# SCH_ad7606__2022-06-28.net
KiCad netlist of a schematic drawn in EasyEDA
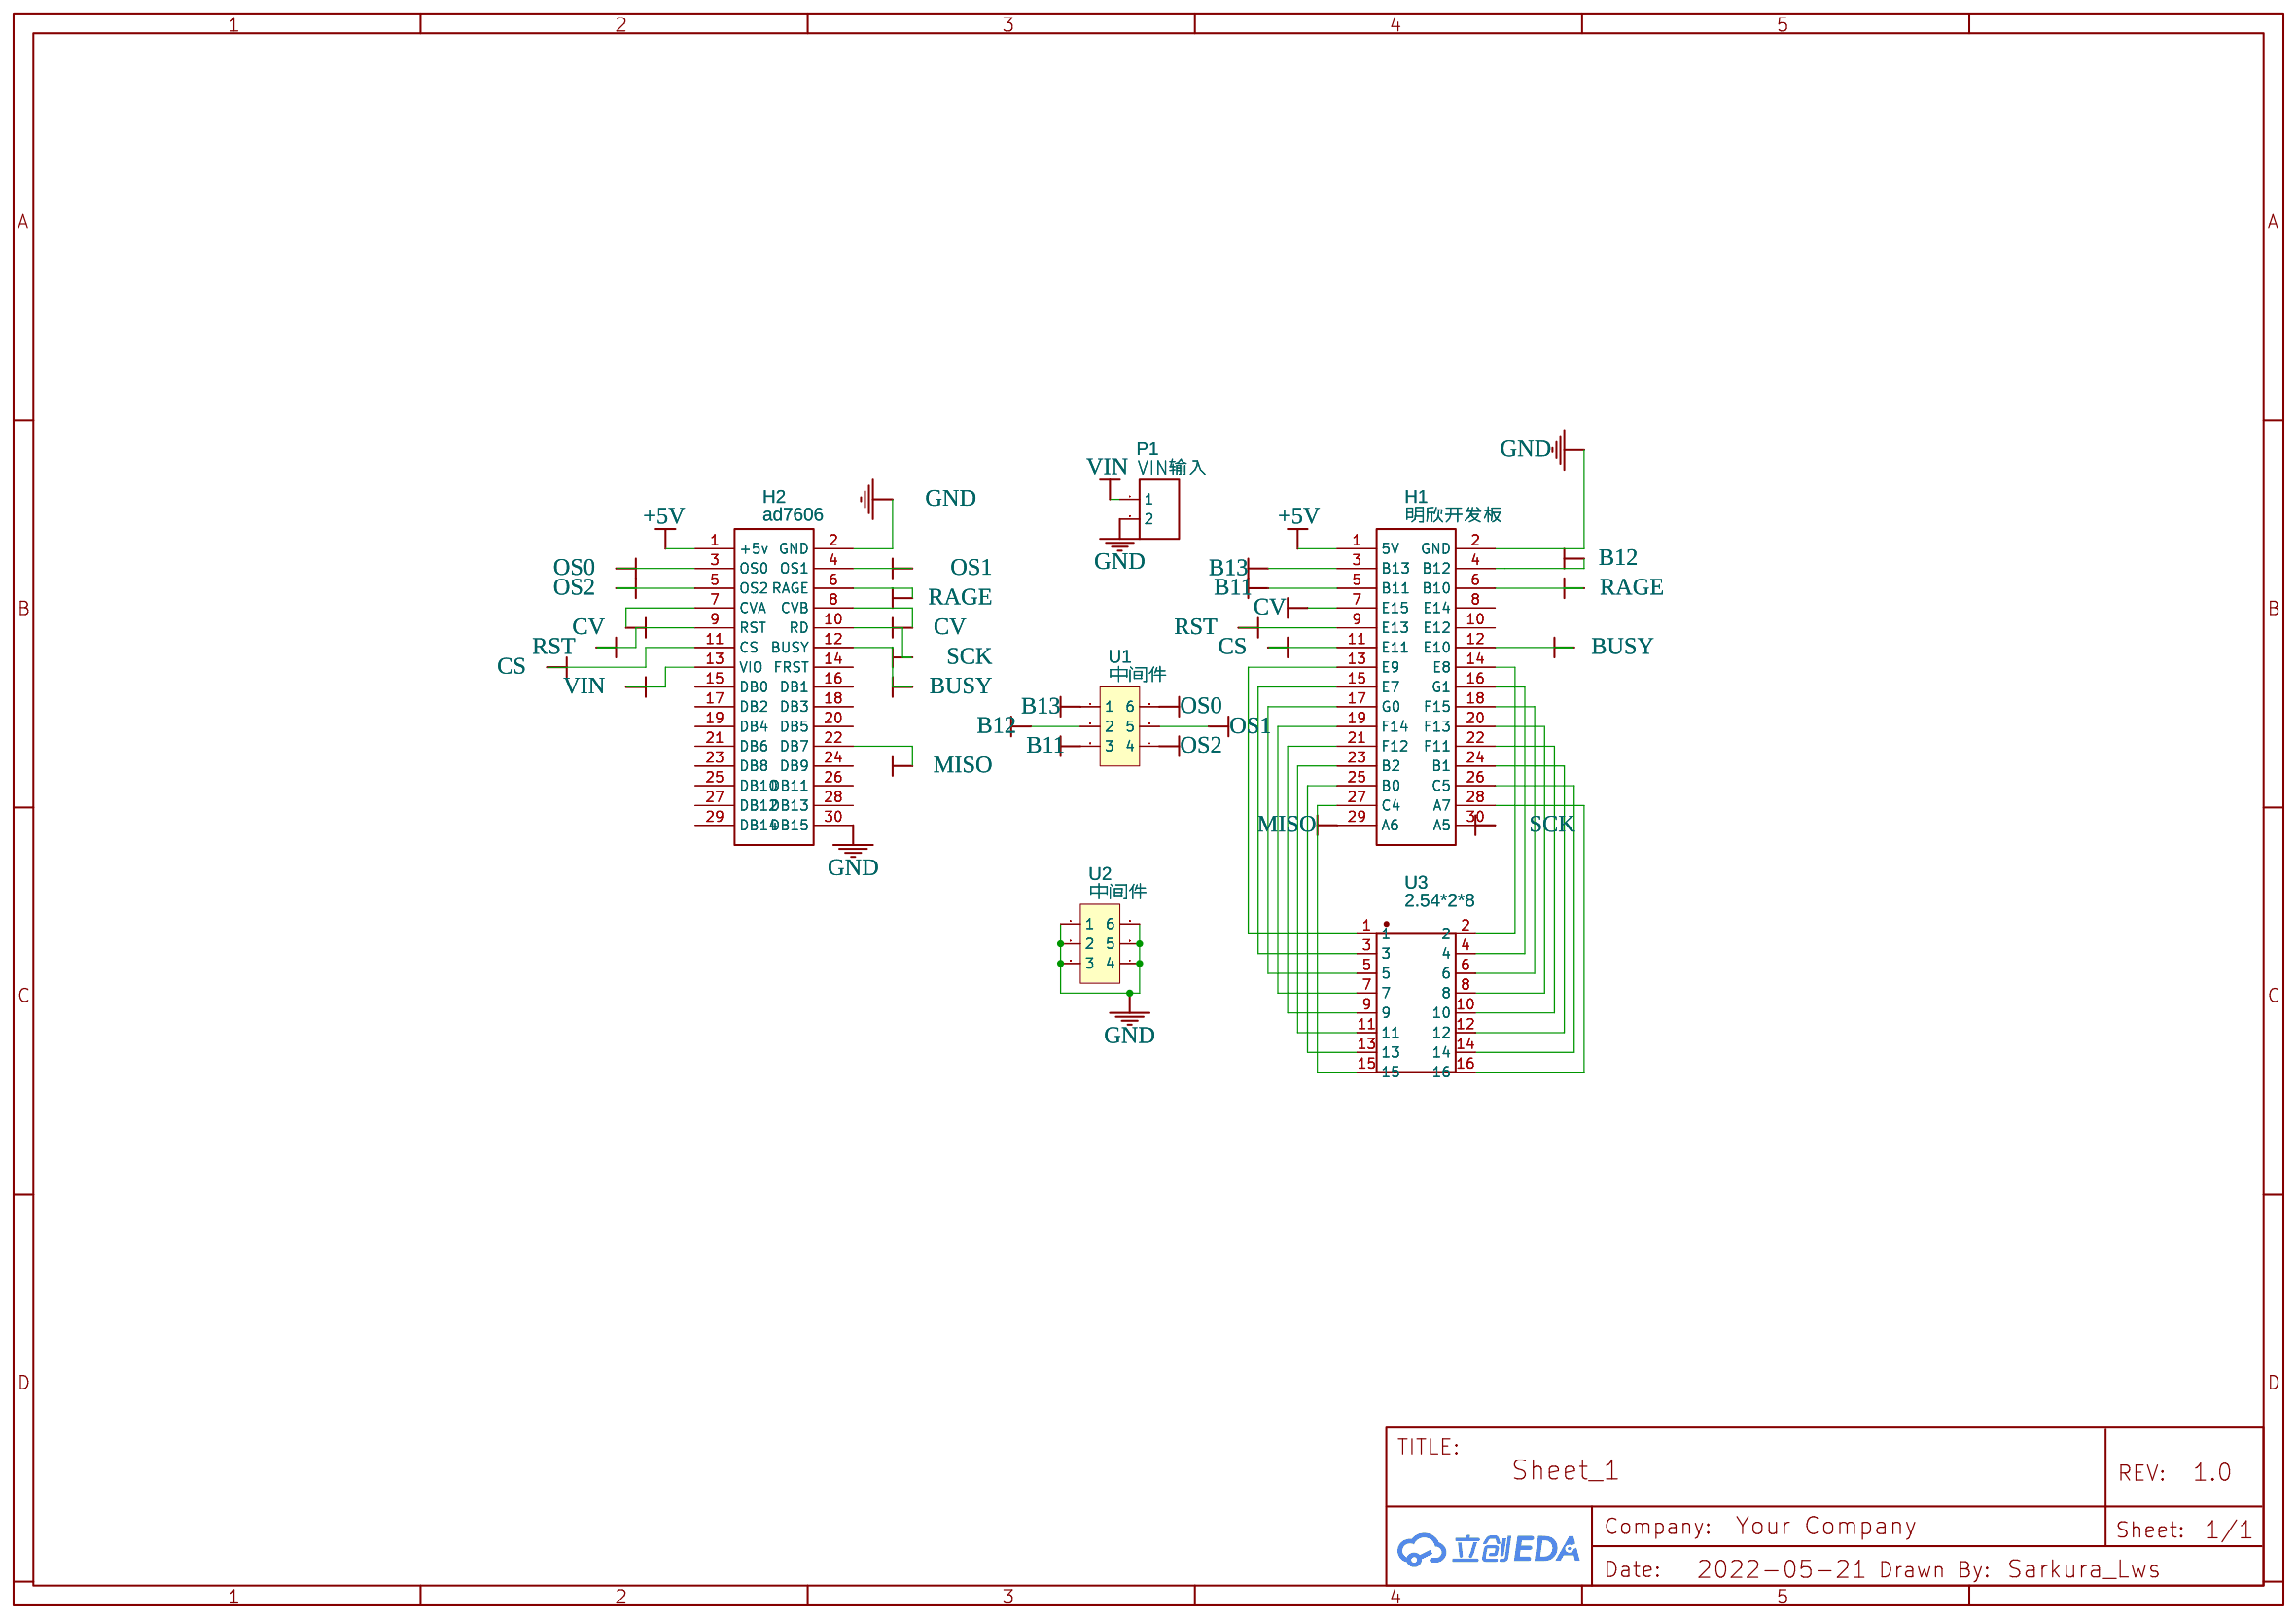
[diagram p0: schematic sheet]

(export (version "E")
  (design (tool "Eeschema 10.0.6"))
  (components
    (comp (ref "H1")
      (value "明欣开发板")
      (fields (field (name "BOM_Supplier Part") "C169817"))
      (libsource (lib "") (part "2*15P 2.54mm_1"))
    )
    (comp (ref "H2")
      (value "ad7606")
      (fields (field (name "BOM_Supplier Part") "C169817"))
      (libsource (lib "") (part "2*15P 2.54mm"))
    )
    (comp (ref "P1")
      (value "VIN输入")
      (fields
        (field (name "BOM_Manufacturer Part") "2.54-1*2PFemale")
        (field (name "BOM_Supplier Part") "C49661")
      )
      (libsource (lib "") (part "Header-Female-2.54_1x2"))
    )
    (comp (ref "U1") (value "中间件") (libsource (lib "") (part "HEADER-2*3-2.54MM")))
    (comp (ref "U2") (value "中间件") (libsource (lib "") (part "HEADER-2*3-2.54MM")))
    (comp (ref "U3") (value "2.54*2*8") (libsource (lib "") (part "2.54*2*8")))
  )
  (nets
    (net (code "1") (name "+5V") (class "Default")
      (node (ref "H1") (pin "1") (pinfunction "5V_1") (pintype "unspecified"))
      (node (ref "H2") (pin "1") (pinfunction "+5v_1") (pintype "unspecified"))
    )
    (net (code "2") (name "B11") (class "Default")
      (node (ref "H1") (pin "5") (pinfunction "B11_5") (pintype "unspecified"))
      (node (ref "U1") (pin "3") (pinfunction "3_3") (pintype "unspecified"))
    )
    (net (code "3") (name "B12") (class "Default")
      (node (ref "H1") (pin "4") (pinfunction "B12_4") (pintype "unspecified"))
      (node (ref "U1") (pin "2") (pinfunction "2_2") (pintype "unspecified"))
    )
    (net (code "4") (name "B13") (class "Default")
      (node (ref "H1") (pin "3") (pinfunction "B13_3") (pintype "unspecified"))
      (node (ref "U1") (pin "1") (pinfunction "1_1") (pintype "unspecified"))
    )
    (net (code "5") (name "BUSY") (class "Default")
      (node (ref "H1") (pin "12") (pinfunction "E10_12") (pintype "unspecified"))
      (node (ref "H2") (pin "12") (pinfunction "BUSY_12") (pintype "unspecified"))
    )
    (net (code "6") (name "CS") (class "Default")
      (node (ref "H1") (pin "11") (pinfunction "E11_11") (pintype "unspecified"))
      (node (ref "H2") (pin "11") (pinfunction "CS_11") (pintype "unspecified"))
    )
    (net (code "7") (name "CV") (class "Default")
      (node (ref "H1") (pin "7") (pinfunction "E15_7") (pintype "unspecified"))
      (node (ref "H2") (pin "7") (pinfunction "CVA_7") (pintype "unspecified"))
      (node (ref "H2") (pin "8") (pinfunction "CVB_8") (pintype "unspecified"))
    )
    (net (code "8") (name "GND") (class "Default")
      (node (ref "H1") (pin "2") (pinfunction "GND_2") (pintype "unspecified"))
      (node (ref "H2") (pin "2") (pinfunction "GND_2") (pintype "unspecified"))
      (node (ref "H2") (pin "30") (pinfunction "DB15_30") (pintype "unspecified"))
      (node (ref "P1") (pin "2") (pinfunction "2_2") (pintype "input"))
      (node (ref "U2") (pin "1") (pinfunction "1_1") (pintype "unspecified"))
      (node (ref "U2") (pin "2") (pinfunction "2_2") (pintype "unspecified"))
      (node (ref "U2") (pin "3") (pinfunction "3_3") (pintype "unspecified"))
      (node (ref "U2") (pin "4") (pinfunction "4_4") (pintype "unspecified"))
      (node (ref "U2") (pin "5") (pinfunction "5_5") (pintype "unspecified"))
      (node (ref "U2") (pin "6") (pinfunction "6_6") (pintype "unspecified"))
    )
    (net (code "9") (name "MISO") (class "Default")
      (node (ref "H1") (pin "29") (pinfunction "A6_29") (pintype "unspecified"))
      (node (ref "H2") (pin "22") (pinfunction "DB7_22") (pintype "unspecified"))
    )
    (net (code "10") (name "Net-(H1-A7)") (class "Default")
      (node (ref "H1") (pin "28") (pinfunction "A7_28") (pintype "unspecified"))
      (node (ref "U3") (pin "16") (pinfunction "16_16") (pintype "unspecified"))
    )
    (net (code "11") (name "Net-(H1-B0)") (class "Default")
      (node (ref "H1") (pin "25") (pinfunction "B0_25") (pintype "unspecified"))
      (node (ref "U3") (pin "13") (pinfunction "13_13") (pintype "unspecified"))
    )
    (net (code "12") (name "Net-(H1-B1)") (class "Default")
      (node (ref "H1") (pin "24") (pinfunction "B1_24") (pintype "unspecified"))
      (node (ref "U3") (pin "12") (pinfunction "12_12") (pintype "unspecified"))
    )
    (net (code "13") (name "Net-(H1-B2)") (class "Default")
      (node (ref "H1") (pin "23") (pinfunction "B2_23") (pintype "unspecified"))
      (node (ref "U3") (pin "11") (pinfunction "11_11") (pintype "unspecified"))
    )
    (net (code "14") (name "Net-(H1-C4)") (class "Default")
      (node (ref "H1") (pin "27") (pinfunction "C4_27") (pintype "unspecified"))
      (node (ref "U3") (pin "15") (pinfunction "15_15") (pintype "unspecified"))
    )
    (net (code "15") (name "Net-(H1-C5)") (class "Default")
      (node (ref "H1") (pin "26") (pinfunction "C5_26") (pintype "unspecified"))
      (node (ref "U3") (pin "14") (pinfunction "14_14") (pintype "unspecified"))
    )
    (net (code "16") (name "Net-(H1-E7)") (class "Default")
      (node (ref "H1") (pin "15") (pinfunction "E7_15") (pintype "unspecified"))
      (node (ref "U3") (pin "3") (pinfunction "3_3") (pintype "unspecified"))
    )
    (net (code "17") (name "Net-(H1-E8)") (class "Default")
      (node (ref "H1") (pin "14") (pinfunction "E8_14") (pintype "unspecified"))
      (node (ref "U3") (pin "2") (pinfunction "2_2") (pintype "unspecified"))
    )
    (net (code "18") (name "Net-(H1-E9)") (class "Default")
      (node (ref "H1") (pin "13") (pinfunction "E9_13") (pintype "unspecified"))
      (node (ref "U3") (pin "1") (pinfunction "1_1") (pintype "unspecified"))
    )
    (net (code "19") (name "Net-(H1-F11)") (class "Default")
      (node (ref "H1") (pin "22") (pinfunction "F11_22") (pintype "unspecified"))
      (node (ref "U3") (pin "10") (pinfunction "10_10") (pintype "unspecified"))
    )
    (net (code "20") (name "Net-(H1-F12)") (class "Default")
      (node (ref "H1") (pin "21") (pinfunction "F12_21") (pintype "unspecified"))
      (node (ref "U3") (pin "9") (pinfunction "9_9") (pintype "unspecified"))
    )
    (net (code "21") (name "Net-(H1-F13)") (class "Default")
      (node (ref "H1") (pin "20") (pinfunction "F13_20") (pintype "unspecified"))
      (node (ref "U3") (pin "8") (pinfunction "8_8") (pintype "unspecified"))
    )
    (net (code "22") (name "Net-(H1-F14)") (class "Default")
      (node (ref "H1") (pin "19") (pinfunction "F14_19") (pintype "unspecified"))
      (node (ref "U3") (pin "7") (pinfunction "7_7") (pintype "unspecified"))
    )
    (net (code "23") (name "Net-(H1-F15)") (class "Default")
      (node (ref "H1") (pin "18") (pinfunction "F15_18") (pintype "unspecified"))
      (node (ref "U3") (pin "6") (pinfunction "6_6") (pintype "unspecified"))
    )
    (net (code "24") (name "Net-(H1-G0)") (class "Default")
      (node (ref "H1") (pin "17") (pinfunction "G0_17") (pintype "unspecified"))
      (node (ref "U3") (pin "5") (pinfunction "5_5") (pintype "unspecified"))
    )
    (net (code "25") (name "Net-(H1-G1)") (class "Default")
      (node (ref "H1") (pin "16") (pinfunction "G1_16") (pintype "unspecified"))
      (node (ref "U3") (pin "4") (pinfunction "4_4") (pintype "unspecified"))
    )
    (net (code "26") (name "OS0") (class "Default")
      (node (ref "H2") (pin "3") (pinfunction "OS0_3") (pintype "unspecified"))
      (node (ref "U1") (pin "6") (pinfunction "6_6") (pintype "unspecified"))
    )
    (net (code "27") (name "OS1") (class "Default")
      (node (ref "H2") (pin "4") (pinfunction "OS1_4") (pintype "unspecified"))
      (node (ref "U1") (pin "5") (pinfunction "5_5") (pintype "unspecified"))
    )
    (net (code "28") (name "OS2") (class "Default")
      (node (ref "H2") (pin "5") (pinfunction "OS2_5") (pintype "unspecified"))
      (node (ref "U1") (pin "4") (pinfunction "4_4") (pintype "unspecified"))
    )
    (net (code "29") (name "RAGE") (class "Default")
      (node (ref "H1") (pin "6") (pinfunction "B10_6") (pintype "unspecified"))
      (node (ref "H2") (pin "6") (pinfunction "RAGE_6") (pintype "unspecified"))
    )
    (net (code "30") (name "RST") (class "Default")
      (node (ref "H1") (pin "9") (pinfunction "E13_9") (pintype "unspecified"))
      (node (ref "H2") (pin "9") (pinfunction "RST_9") (pintype "unspecified"))
    )
    (net (code "31") (name "SCK") (class "Default")
      (node (ref "H1") (pin "30") (pinfunction "A5_30") (pintype "unspecified"))
      (node (ref "H2") (pin "10") (pinfunction "RD_10") (pintype "unspecified"))
    )
    (net (code "32") (name "VIN") (class "Default")
      (node (ref "H2") (pin "13") (pinfunction "VIO_13") (pintype "unspecified"))
      (node (ref "P1") (pin "1") (pinfunction "1_1") (pintype "input"))
    )
    (net (code "33") (name "unconnected-(H1-E12-Pad10)") (class "Default")
      (node (ref "H1") (pin "10") (pinfunction "E12_10") (pintype "unspecified"))
    )
    (net (code "34") (name "unconnected-(H1-E14-Pad8)") (class "Default")
      (node (ref "H1") (pin "8") (pinfunction "E14_8") (pintype "unspecified"))
    )
    (net (code "35") (name "unconnected-(H2-DB0-Pad15)") (class "Default")
      (node (ref "H2") (pin "15") (pinfunction "DB0_15") (pintype "unspecified"))
    )
    (net (code "36") (name "unconnected-(H2-DB1-Pad16)") (class "Default")
      (node (ref "H2") (pin "16") (pinfunction "DB1_16") (pintype "unspecified"))
    )
    (net (code "37") (name "unconnected-(H2-DB2-Pad17)") (class "Default")
      (node (ref "H2") (pin "17") (pinfunction "DB2_17") (pintype "unspecified"))
    )
    (net (code "38") (name "unconnected-(H2-DB3-Pad18)") (class "Default")
      (node (ref "H2") (pin "18") (pinfunction "DB3_18") (pintype "unspecified"))
    )
    (net (code "39") (name "unconnected-(H2-DB4-Pad19)") (class "Default")
      (node (ref "H2") (pin "19") (pinfunction "DB4_19") (pintype "unspecified"))
    )
    (net (code "40") (name "unconnected-(H2-DB5-Pad20)") (class "Default")
      (node (ref "H2") (pin "20") (pinfunction "DB5_20") (pintype "unspecified"))
    )
    (net (code "41") (name "unconnected-(H2-DB6-Pad21)") (class "Default")
      (node (ref "H2") (pin "21") (pinfunction "DB6_21") (pintype "unspecified"))
    )
    (net (code "42") (name "unconnected-(H2-DB8-Pad23)") (class "Default")
      (node (ref "H2") (pin "23") (pinfunction "DB8_23") (pintype "unspecified"))
    )
    (net (code "43") (name "unconnected-(H2-DB9-Pad24)") (class "Default")
      (node (ref "H2") (pin "24") (pinfunction "DB9_24") (pintype "unspecified"))
    )
    (net (code "44") (name "unconnected-(H2-DB10-Pad25)") (class "Default")
      (node (ref "H2") (pin "25") (pinfunction "DB10_25") (pintype "unspecified"))
    )
    (net (code "45") (name "unconnected-(H2-DB11-Pad26)") (class "Default")
      (node (ref "H2") (pin "26") (pinfunction "DB11_26") (pintype "unspecified"))
    )
    (net (code "46") (name "unconnected-(H2-DB12-Pad27)") (class "Default")
      (node (ref "H2") (pin "27") (pinfunction "DB12_27") (pintype "unspecified"))
    )
    (net (code "47") (name "unconnected-(H2-DB13-Pad28)") (class "Default")
      (node (ref "H2") (pin "28") (pinfunction "DB13_28") (pintype "unspecified"))
    )
    (net (code "48") (name "unconnected-(H2-DB14-Pad29)") (class "Default")
      (node (ref "H2") (pin "29") (pinfunction "DB14_29") (pintype "unspecified"))
    )
    (net (code "49") (name "unconnected-(H2-FRST-Pad14)") (class "Default")
      (node (ref "H2") (pin "14") (pinfunction "FRST_14") (pintype "unspecified"))
    )
  )
)
